# Pre_schV2_1.net
KiCad netlist of a schematic drawn in EAGLE
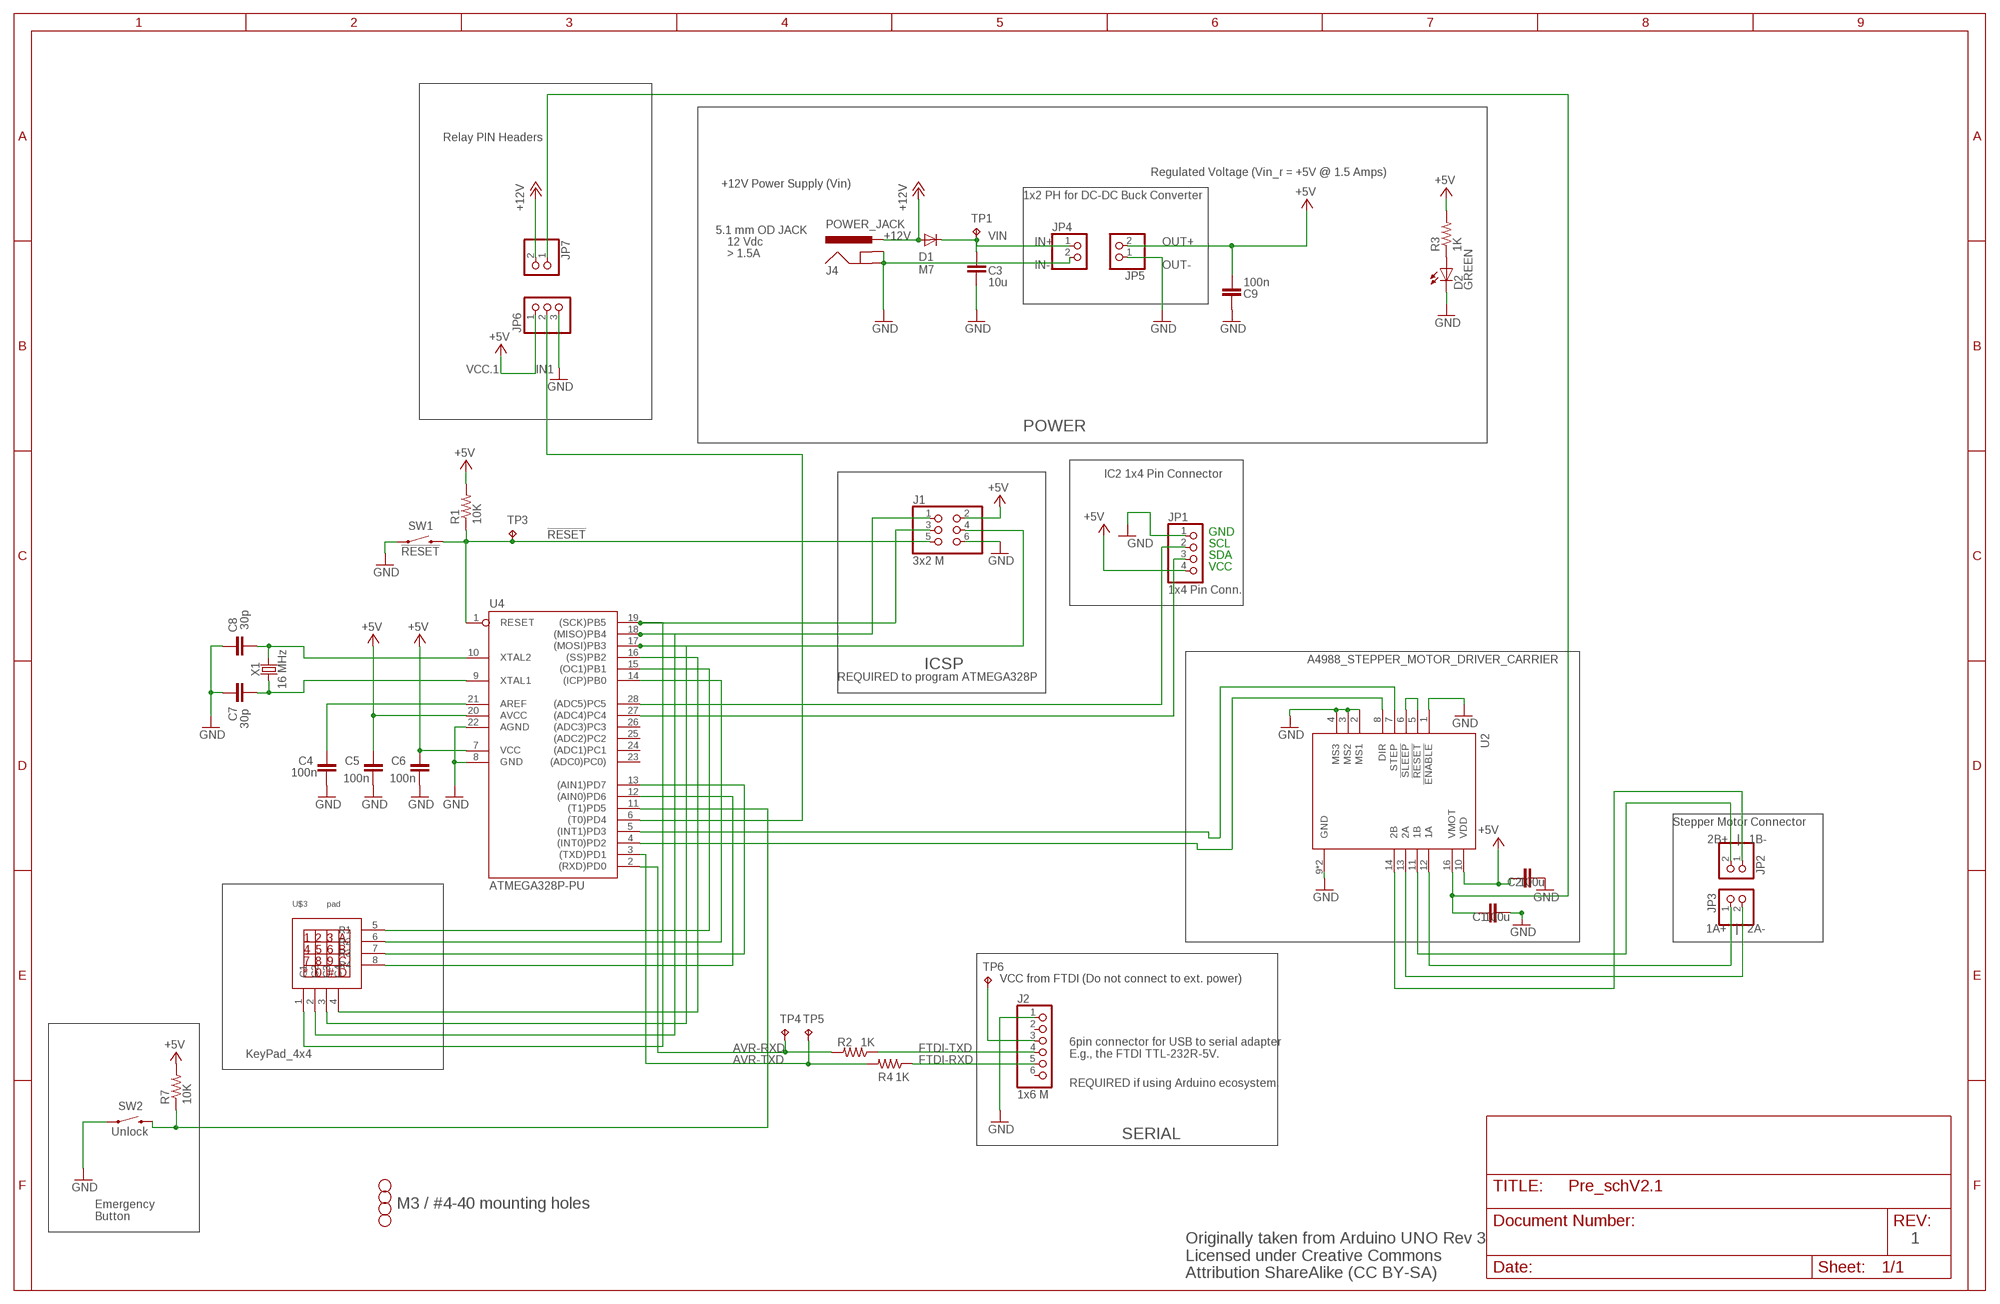
[diagram p0: schematic, sheet 1]

(export (version "E")
  (design (tool "Eeschema 10.0.6"))
  (components
    (comp (ref "C1")
      (value "100u")
      (footprint "eagle-import:C0805K")
      (fields (field (name "MFR") "Samsung") (field (name "MPN") "CL21B104KBCNNNC"))
      (libsource (lib "eagle-import") (part "C-EUC0805K"))
    )
    (comp (ref "C2")
      (value "100u")
      (footprint "eagle-import:C0805K")
      (fields (field (name "MFR") "Samsung") (field (name "MPN") "CL21B104KBCNNNC"))
      (libsource (lib "eagle-import") (part "C-EUC0805K"))
    )
    (comp (ref "C3")
      (value "10u")
      (footprint "eagle-import:C0805K")
      (fields (field (name "MFR") "Samsung") (field (name "MPN") "CL21A106KOQNNNG"))
      (libsource (lib "eagle-import") (part "C-EUC0805K"))
    )
    (comp (ref "C4")
      (value "100n")
      (footprint "eagle-import:C0805K")
      (fields (field (name "MFR") "Samsung") (field (name "MPN") "CL21B104KBCNNNC"))
      (libsource (lib "eagle-import") (part "C-EUC0805K"))
    )
    (comp (ref "C5")
      (value "100n")
      (footprint "eagle-import:C0805K")
      (fields (field (name "MFR") "Samsung") (field (name "MPN") "CL21B104KBCNNNC"))
      (libsource (lib "eagle-import") (part "C-EUC0805K"))
    )
    (comp (ref "C6")
      (value "100n")
      (footprint "eagle-import:C0805K")
      (fields (field (name "MFR") "Samsung") (field (name "MPN") "CL21B104KBCNNNC"))
      (libsource (lib "eagle-import") (part "C-EUC0805K"))
    )
    (comp (ref "C7")
      (value "30p")
      (footprint "eagle-import:C0805K")
      (fields (field (name "MFR") "Samsung") (field (name "MPN") "CL21C180JBANNNC"))
      (libsource (lib "eagle-import") (part "C-EUC0805K"))
    )
    (comp (ref "C8")
      (value "30p")
      (footprint "eagle-import:C0805K")
      (fields (field (name "MFR") "Samsung") (field (name "MPN") "CL21C300JBANNNC"))
      (libsource (lib "eagle-import") (part "C-EUC0805K"))
    )
    (comp (ref "C9")
      (value "100n")
      (footprint "eagle-import:C0805K")
      (fields (field (name "MFR") "Samsung") (field (name "MPN") "CL21B104KBCNNNC"))
      (libsource (lib "eagle-import") (part "C-EUC0805K"))
    )
    (comp (ref "D1")
      (value "M7")
      (footprint "eagle-import:SMB")
      (fields (field (name "MFR") "SMC Diode") (field (name "MPN") "10BQ030TR"))
      (libsource (lib "eagle-import") (part "DIODE-SMB"))
    )
    (comp (ref "D2")
      (value "GREEN")
      (footprint "eagle-import:CHIP-LED0805")
      (fields (field (name "MFR") "Würth Elektronik") (field (name "MPN") "150080GS75000"))
      (libsource (lib "eagle-import") (part "LEDCHIP-LED0805"))
    )
    (comp (ref "H1")
      (value "STAND-OFF")
      (footprint "eagle-import:STAND-OFF")
      (libsource (lib "eagle-import") (part "STAND-OFF"))
    )
    (comp (ref "H2")
      (value "STAND-OFF")
      (footprint "eagle-import:STAND-OFF")
      (libsource (lib "eagle-import") (part "STAND-OFF"))
    )
    (comp (ref "H3")
      (value "STAND-OFF")
      (footprint "eagle-import:STAND-OFF")
      (libsource (lib "eagle-import") (part "STAND-OFF"))
    )
    (comp (ref "H4")
      (value "STAND-OFF")
      (footprint "eagle-import:STAND-OFF")
      (libsource (lib "eagle-import") (part "STAND-OFF"))
    )
    (comp (ref "J1")
      (value "3x2 M")
      (footprint "eagle-import:2X03")
      (fields (field (name "MFR") "Harwin") (field (name "MPN") "M20-9980345"))
      (libsource (lib "eagle-import") (part "PINHD-2X3"))
    )
    (comp (ref "J2")
      (value "1x6 M")
      (footprint "eagle-import:1X06")
      (fields (field (name "MFR") "Sullins") (field (name "MPN") "PRPC006SAAN-RC"))
      (libsource (lib "eagle-import") (part "PINHD-1X6"))
    )
    (comp (ref "J4")
      (value "POWER_JACK")
      (footprint "eagle-import:POWER_JACK_PTH")
      (fields (field (name "MFR") "CUI") (field (name "MPN") "PJ-202A"))
      (libsource (lib "eagle-import") (part "POWER_JACK"))
    )
    (comp (ref "JP1")
      (value "1x4 Pin Conn.")
      (footprint "eagle-import:1X04")
      (libsource (lib "eagle-import") (part "PINHD-1X4"))
    )
    (comp (ref "JP2")
      (value "2B+ | 1B-")
      (footprint "eagle-import:1X02")
      (libsource (lib "eagle-import") (part "PINHD-1X2"))
    )
    (comp (ref "JP3")
      (value "1A+ | 2A-")
      (footprint "eagle-import:1X02")
      (libsource (lib "eagle-import") (part "PINHD-1X2"))
    )
    (comp (ref "JP4")
      (value "PINHD-1X2")
      (footprint "eagle-import:1X02")
      (libsource (lib "eagle-import") (part "PINHD-1X2"))
    )
    (comp (ref "JP5")
      (value "PINHD-1X2")
      (footprint "eagle-import:1X02")
      (libsource (lib "eagle-import") (part "PINHD-1X2"))
    )
    (comp (ref "JP6")
      (value "PINHD-1X3")
      (footprint "eagle-import:1X03")
      (libsource (lib "eagle-import") (part "PINHD-1X3"))
    )
    (comp (ref "JP7")
      (value "PINHD-1X2")
      (footprint "eagle-import:1X02")
      (libsource (lib "eagle-import") (part "PINHD-1X2"))
    )
    (comp (ref "R1")
      (value "10K")
      (footprint "eagle-import:R0805")
      (fields (field (name "MFR") "Yageo") (field (name "MPN") "RC0805FR-0710KL"))
      (libsource (lib "eagle-import") (part "R-US_R0805"))
    )
    (comp (ref "R2")
      (value "1K")
      (footprint "eagle-import:R0805")
      (fields (field (name "MFR") "Yageo") (field (name "MPN") "RC0805FR-071KL"))
      (libsource (lib "eagle-import") (part "R-US_R0805"))
    )
    (comp (ref "R3")
      (value "1K")
      (footprint "eagle-import:R0805")
      (fields (field (name "MFR") "Yageo") (field (name "MPN") "RC0805FR-071KL"))
      (libsource (lib "eagle-import") (part "R-US_R0805"))
    )
    (comp (ref "R4")
      (value "1K")
      (footprint "eagle-import:R0805")
      (fields (field (name "MFR") "Yageo") (field (name "MPN") "RC0805FR-071KL"))
      (libsource (lib "eagle-import") (part "R-US_R0805"))
    )
    (comp (ref "R7")
      (value "10K")
      (footprint "eagle-import:R0805")
      (fields (field (name "MFR") "Yageo") (field (name "MPN") "RC0805FR-0710KL"))
      (libsource (lib "eagle-import") (part "R-US_R0805"))
    )
    (comp (ref "SW1")
      (value "!RESET")
      (footprint "eagle-import:TACTILE_SWITCH_SMD")
      (fields (field (name "MFR") "C&K") (field (name "MPN") "RS-187R05A2-DS MT RT"))
      (libsource (lib "eagle-import") (part "SWITCH-MOMENTARY-2SMD"))
    )
    (comp (ref "SW2")
      (value "Unlock")
      (footprint "eagle-import:TACTILE_SWITCH_SMD")
      (fields (field (name "MFR") "C&K") (field (name "MPN") "RS-187R05A2-DS MT RT"))
      (libsource (lib "eagle-import") (part "SWITCH-MOMENTARY-2SMD"))
    )
    (comp (ref "TP1")
      (value "TPPAD1-13")
      (footprint "eagle-import:P1-13")
      (libsource (lib "eagle-import") (part "TPPAD1-13"))
    )
    (comp (ref "TP3")
      (value "TPPAD1-13")
      (footprint "eagle-import:P1-13")
      (libsource (lib "eagle-import") (part "TPPAD1-13"))
    )
    (comp (ref "TP4")
      (value "TPPAD1-13")
      (footprint "eagle-import:P1-13")
      (libsource (lib "eagle-import") (part "TPPAD1-13"))
    )
    (comp (ref "TP5")
      (value "TPPAD1-13")
      (footprint "eagle-import:P1-13")
      (libsource (lib "eagle-import") (part "TPPAD1-13"))
    )
    (comp (ref "TP6")
      (value "TPPAD1-13")
      (footprint "eagle-import:P1-13")
      (libsource (lib "eagle-import") (part "TPPAD1-13"))
    )
    (comp (ref "U$3")
      (value "pad")
      (footprint "eagle-import:KEYPAD4X4")
      (libsource (lib "eagle-import") (part "KEYPAD4X4"))
    )
    (comp (ref "U2")
      (value "A4988_STEPPER_MOTOR_DRIVER_CARRIER")
      (footprint "eagle-import:MODULE_A4988_STEPPER_MOTOR_DRIVER_CARRIER")
      (fields (field (name "MF") "Pololu") (field (name "MP") "A4988 STEPPER MOTOR DRIVER CARRIER"))
      (libsource (lib "eagle-import") (part "A4988_STEPPER_MOTOR_DRIVER_CARRIER"))
    )
    (comp (ref "U4")
      (value "ATMEGA328P-PU")
      (footprint "eagle-import:DIL28-3")
      (fields (field (name "MFR") "Microchip"))
      (libsource (lib "eagle-import") (part "ATMEGA328P-PU"))
    )
    (comp (ref "X1")
      (value "16 MHz")
      (footprint "eagle-import:HC49UP")
      (fields (field (name "MFR") "ECS") (field (name "MPN") "ECS-160-18-5PX-TR"))
      (libsource (lib "eagle-import") (part "CRYSTALSMD-HC49UP"))
    )
  )
  (nets
    (net (code "1") (name "+5V") (class "Default")
      (node (ref "C2") (pin "2") (pinfunction "2_2") (pintype "passive"))
      (node (ref "C5") (pin "2") (pinfunction "2_2") (pintype "passive"))
      (node (ref "C6") (pin "2") (pinfunction "2_2") (pintype "passive"))
      (node (ref "C9") (pin "2") (pinfunction "2_2") (pintype "passive"))
      (node (ref "J1") (pin "2") (pinfunction "2_2") (pintype "passive"))
      (node (ref "JP1") (pin "4") (pinfunction "4_4") (pintype "passive"))
      (node (ref "JP5") (pin "2") (pinfunction "2_2") (pintype "passive"))
      (node (ref "JP6") (pin "1") (pinfunction "1_1") (pintype "passive"))
      (node (ref "R1") (pin "2") (pinfunction "2_2") (pintype "passive"))
      (node (ref "R3") (pin "2") (pinfunction "2_2") (pintype "passive"))
      (node (ref "R7") (pin "2") (pinfunction "2_2") (pintype "passive"))
      (node (ref "U2") (pin "10") (pinfunction "VDD_10") (pintype "power_in"))
      (node (ref "U4") (pin "20") (pinfunction "AVCC_20") (pintype "power_in"))
      (node (ref "U4") (pin "7") (pinfunction "VCC_7") (pintype "power_in"))
    )
    (net (code "2") (name "+12V") (class "Default")
      (node (ref "D1") (pin "A") (pinfunction "A_A") (pintype "passive"))
      (node (ref "J4") (pin "PWR") (pinfunction "PWR_PWR") (pintype "bidirectional"))
      (node (ref "JP7") (pin "2") (pinfunction "2_2") (pintype "passive"))
    )
    (net (code "3") (name "/AVR-RXD") (class "Default")
      (node (ref "R2") (pin "2") (pinfunction "2_2") (pintype "passive"))
      (node (ref "TP4") (pin "TP") (pinfunction "TP_TP") (pintype "input"))
      (node (ref "U4") (pin "2") (pinfunction "(RXD)PD0_2") (pintype "bidirectional"))
    )
    (net (code "4") (name "/AVR-TXD") (class "Default")
      (node (ref "R4") (pin "2") (pinfunction "2_2") (pintype "passive"))
      (node (ref "TP5") (pin "TP") (pinfunction "TP_TP") (pintype "input"))
      (node (ref "U4") (pin "3") (pinfunction "(TXD)PD1_3") (pintype "bidirectional"))
    )
    (net (code "5") (name "/FTDI-RXD") (class "Default")
      (node (ref "J2") (pin "5") (pinfunction "5_5") (pintype "passive"))
      (node (ref "R4") (pin "1") (pinfunction "1_1") (pintype "passive"))
    )
    (net (code "6") (name "/FTDI-TXD") (class "Default")
      (node (ref "J2") (pin "4") (pinfunction "4_4") (pintype "passive"))
      (node (ref "R2") (pin "1") (pinfunction "1_1") (pintype "passive"))
    )
    (net (code "7") (name "/VIN") (class "Default")
      (node (ref "C3") (pin "1") (pinfunction "1_1") (pintype "passive"))
      (node (ref "D1") (pin "C") (pinfunction "C_C") (pintype "passive"))
      (node (ref "JP4") (pin "1") (pinfunction "1_1") (pintype "passive"))
      (node (ref "TP1") (pin "TP") (pinfunction "TP_TP") (pintype "input"))
    )
    (net (code "8") (name "/~{RESET}") (class "Default")
      (node (ref "J1") (pin "5") (pinfunction "5_5") (pintype "passive"))
      (node (ref "R1") (pin "1") (pinfunction "1_1") (pintype "passive"))
      (node (ref "SW1") (pin "3") (pinfunction "2_3") (pintype "passive"))
      (node (ref "TP3") (pin "TP") (pinfunction "TP_TP") (pintype "input"))
      (node (ref "U4") (pin "1") (pinfunction "RESET_1") (pintype "input"))
    )
    (net (code "9") (name "GND") (class "Default")
      (node (ref "C1") (pin "1") (pinfunction "1_1") (pintype "passive"))
      (node (ref "C2") (pin "1") (pinfunction "1_1") (pintype "passive"))
      (node (ref "C3") (pin "2") (pinfunction "2_2") (pintype "passive"))
      (node (ref "C4") (pin "1") (pinfunction "1_1") (pintype "passive"))
      (node (ref "C5") (pin "1") (pinfunction "1_1") (pintype "passive"))
      (node (ref "C6") (pin "1") (pinfunction "1_1") (pintype "passive"))
      (node (ref "C7") (pin "2") (pinfunction "2_2") (pintype "passive"))
      (node (ref "C8") (pin "2") (pinfunction "2_2") (pintype "passive"))
      (node (ref "C9") (pin "1") (pinfunction "1_1") (pintype "passive"))
      (node (ref "D2") (pin "C") (pinfunction "C_C") (pintype "passive"))
      (node (ref "J1") (pin "6") (pinfunction "6_6") (pintype "passive"))
      (node (ref "J2") (pin "1") (pinfunction "1_1") (pintype "passive"))
      (node (ref "J4") (pin "GND") (pinfunction "GND_GND") (pintype "bidirectional"))
      (node (ref "J4") (pin "GNDBREAK") (pinfunction "GNDBREAK_GNDBREAK") (pintype "bidirectional"))
      (node (ref "JP1") (pin "1") (pinfunction "1_1") (pintype "passive"))
      (node (ref "JP4") (pin "2") (pinfunction "2_2") (pintype "passive"))
      (node (ref "JP5") (pin "1") (pinfunction "1_1") (pintype "passive"))
      (node (ref "JP6") (pin "3") (pinfunction "3_3") (pintype "passive"))
      (node (ref "SW1") (pin "1") (pinfunction "1_1") (pintype "passive"))
      (node (ref "SW2") (pin "1") (pinfunction "1_1") (pintype "passive"))
      (node (ref "U2") (pin "1") (pinfunction "~{ENABLE}_1") (pintype "input"))
      (node (ref "U2") (pin "15") (pinfunction "GND_15") (pintype "power_in"))
      (node (ref "U2") (pin "2") (pinfunction "MS1_2") (pintype "input"))
      (node (ref "U2") (pin "3") (pinfunction "MS2_3") (pintype "input"))
      (node (ref "U2") (pin "4") (pinfunction "MS3_4") (pintype "input"))
      (node (ref "U2") (pin "9") (pinfunction "GND_9") (pintype "power_in"))
      (node (ref "U4") (pin "22") (pinfunction "AGND_22") (pintype "power_in"))
      (node (ref "U4") (pin "8") (pinfunction "GND_8") (pintype "power_in"))
    )
    (net (code "10") (name "Net-(D2-PadA)") (class "Default")
      (node (ref "D2") (pin "A") (pinfunction "A_A") (pintype "passive"))
      (node (ref "R3") (pin "1") (pinfunction "1_1") (pintype "passive"))
    )
    (net (code "11") (name "Net-(J2-Pad3)") (class "Default")
      (node (ref "J2") (pin "3") (pinfunction "3_3") (pintype "passive"))
      (node (ref "TP6") (pin "TP") (pinfunction "TP_TP") (pintype "input"))
    )
    (net (code "12") (name "Net-(SW2-2)") (class "Default")
      (node (ref "R7") (pin "1") (pinfunction "1_1") (pintype "passive"))
      (node (ref "SW2") (pin "3") (pinfunction "2_3") (pintype "passive"))
      (node (ref "U4") (pin "11") (pinfunction "(T1)PD5_11") (pintype "bidirectional"))
    )
    (net (code "13") (name "Net-(U$3-C1)") (class "Default")
      (node (ref "J1") (pin "3") (pinfunction "3_3") (pintype "passive"))
      (node (ref "U$3") (pin "1") (pinfunction "C1_1") (pintype "bidirectional"))
      (node (ref "U4") (pin "19") (pinfunction "(SCK)PB5_19") (pintype "bidirectional"))
    )
    (net (code "14") (name "Net-(U$3-C2)") (class "Default")
      (node (ref "J1") (pin "1") (pinfunction "1_1") (pintype "passive"))
      (node (ref "U$3") (pin "2") (pinfunction "C2_2") (pintype "bidirectional"))
      (node (ref "U4") (pin "18") (pinfunction "(MISO)PB4_18") (pintype "bidirectional"))
    )
    (net (code "15") (name "Net-(U$3-C3)") (class "Default")
      (node (ref "J1") (pin "4") (pinfunction "4_4") (pintype "passive"))
      (node (ref "U$3") (pin "3") (pinfunction "C3_3") (pintype "bidirectional"))
      (node (ref "U4") (pin "17") (pinfunction "(MOSI)PB3_17") (pintype "bidirectional"))
    )
    (net (code "16") (name "Net-(U$3-C4)") (class "Default")
      (node (ref "U$3") (pin "4") (pinfunction "C4_4") (pintype "bidirectional"))
      (node (ref "U4") (pin "16") (pinfunction "(SS)PB2_16") (pintype "bidirectional"))
    )
    (net (code "17") (name "Net-(U$3-R1)") (class "Default")
      (node (ref "U$3") (pin "5") (pinfunction "R1_5") (pintype "bidirectional"))
      (node (ref "U4") (pin "15") (pinfunction "(OC1)PB1_15") (pintype "bidirectional"))
    )
    (net (code "18") (name "Net-(U$3-R2)") (class "Default")
      (node (ref "U$3") (pin "6") (pinfunction "R2_6") (pintype "bidirectional"))
      (node (ref "U4") (pin "14") (pinfunction "(ICP)PB0_14") (pintype "bidirectional"))
    )
    (net (code "19") (name "Net-(U$3-R3)") (class "Default")
      (node (ref "U$3") (pin "7") (pinfunction "R3_7") (pintype "bidirectional"))
      (node (ref "U4") (pin "13") (pinfunction "(AIN1)PD7_13") (pintype "bidirectional"))
    )
    (net (code "20") (name "Net-(U$3-R4)") (class "Default")
      (node (ref "U$3") (pin "8") (pinfunction "R4_8") (pintype "bidirectional"))
      (node (ref "U4") (pin "12") (pinfunction "(AIN0)PD6_12") (pintype "bidirectional"))
    )
    (net (code "21") (name "Net-(U2-1A)") (class "Default")
      (node (ref "JP3") (pin "1") (pinfunction "1_1") (pintype "passive"))
      (node (ref "U2") (pin "12") (pinfunction "1A_12") (pintype "output"))
    )
    (net (code "22") (name "Net-(U2-1B)") (class "Default")
      (node (ref "JP2") (pin "2") (pinfunction "2_2") (pintype "passive"))
      (node (ref "U2") (pin "11") (pinfunction "1B_11") (pintype "output"))
    )
    (net (code "23") (name "Net-(U2-2A)") (class "Default")
      (node (ref "JP3") (pin "2") (pinfunction "2_2") (pintype "passive"))
      (node (ref "U2") (pin "13") (pinfunction "2A_13") (pintype "output"))
    )
    (net (code "24") (name "Net-(U2-2B)") (class "Default")
      (node (ref "JP2") (pin "1") (pinfunction "1_1") (pintype "passive"))
      (node (ref "U2") (pin "14") (pinfunction "2B_14") (pintype "output"))
    )
    (net (code "25") (name "Net-(U2-DIR)") (class "Default")
      (node (ref "U2") (pin "8") (pinfunction "DIR_8") (pintype "input"))
      (node (ref "U4") (pin "4") (pinfunction "(INT0)PD2_4") (pintype "bidirectional"))
    )
    (net (code "26") (name "Net-(U2-STEP)") (class "Default")
      (node (ref "U2") (pin "7") (pinfunction "STEP_7") (pintype "input"))
      (node (ref "U4") (pin "5") (pinfunction "(INT1)PD3_5") (pintype "bidirectional"))
    )
    (net (code "27") (name "Net-(U2-VMOT)") (class "Default")
      (node (ref "C1") (pin "2") (pinfunction "2_2") (pintype "passive"))
      (node (ref "JP7") (pin "1") (pinfunction "1_1") (pintype "passive"))
      (node (ref "U2") (pin "16") (pinfunction "VMOT_16") (pintype "power_in"))
    )
    (net (code "28") (name "Net-(U2-~{RESET})") (class "Default")
      (node (ref "U2") (pin "5") (pinfunction "~{RESET}_5") (pintype "input"))
      (node (ref "U2") (pin "6") (pinfunction "~{SLEEP}_6") (pintype "input"))
    )
    (net (code "29") (name "Net-(U4-(ADC4)PC4)") (class "Default")
      (node (ref "JP1") (pin "3") (pinfunction "3_3") (pintype "passive"))
      (node (ref "U4") (pin "27") (pinfunction "(ADC4)PC4_27") (pintype "bidirectional"))
    )
    (net (code "30") (name "Net-(U4-(ADC5)PC5)") (class "Default")
      (node (ref "JP1") (pin "2") (pinfunction "2_2") (pintype "passive"))
      (node (ref "U4") (pin "28") (pinfunction "(ADC5)PC5_28") (pintype "bidirectional"))
    )
    (net (code "31") (name "Net-(U4-(T0)PD4)") (class "Default")
      (node (ref "JP6") (pin "2") (pinfunction "2_2") (pintype "passive"))
      (node (ref "U4") (pin "6") (pinfunction "(T0)PD4_6") (pintype "bidirectional"))
    )
    (net (code "32") (name "Net-(U4-AREF)") (class "Default")
      (node (ref "C4") (pin "2") (pinfunction "2_2") (pintype "passive"))
      (node (ref "U4") (pin "21") (pinfunction "AREF_21") (pintype "passive"))
    )
    (net (code "33") (name "Net-(U4-XTAL1)") (class "Default")
      (node (ref "C7") (pin "1") (pinfunction "1_1") (pintype "passive"))
      (node (ref "U4") (pin "9") (pinfunction "XTAL1_9") (pintype "bidirectional"))
      (node (ref "X1") (pin "1") (pinfunction "1_1") (pintype "passive"))
    )
    (net (code "34") (name "Net-(U4-XTAL2)") (class "Default")
      (node (ref "C8") (pin "1") (pinfunction "1_1") (pintype "passive"))
      (node (ref "U4") (pin "10") (pinfunction "XTAL2_10") (pintype "bidirectional"))
      (node (ref "X1") (pin "2") (pinfunction "2_2") (pintype "passive"))
    )
    (net (code "35") (name "unconnected-(J2-Pad2)") (class "Default")
      (node (ref "J2") (pin "2") (pinfunction "2_2") (pintype "passive"))
    )
    (net (code "36") (name "unconnected-(J2-Pad6)") (class "Default")
      (node (ref "J2") (pin "6") (pinfunction "6_6") (pintype "passive"))
    )
    (net (code "37") (name "unconnected-(U4-(ADC0)PC0)-Pad23)") (class "Default")
      (node (ref "U4") (pin "23") (pinfunction "(ADC0)PC0)_23") (pintype "bidirectional"))
    )
    (net (code "38") (name "unconnected-(U4-(ADC1)PC1-Pad24)") (class "Default")
      (node (ref "U4") (pin "24") (pinfunction "(ADC1)PC1_24") (pintype "bidirectional"))
    )
    (net (code "39") (name "unconnected-(U4-(ADC2)PC2-Pad25)") (class "Default")
      (node (ref "U4") (pin "25") (pinfunction "(ADC2)PC2_25") (pintype "bidirectional"))
    )
    (net (code "40") (name "unconnected-(U4-(ADC3)PC3-Pad26)") (class "Default")
      (node (ref "U4") (pin "26") (pinfunction "(ADC3)PC3_26") (pintype "bidirectional"))
    )
  )
)
